# Cockpit-shield.net
KiCad netlist of a schematic drawn in EAGLE
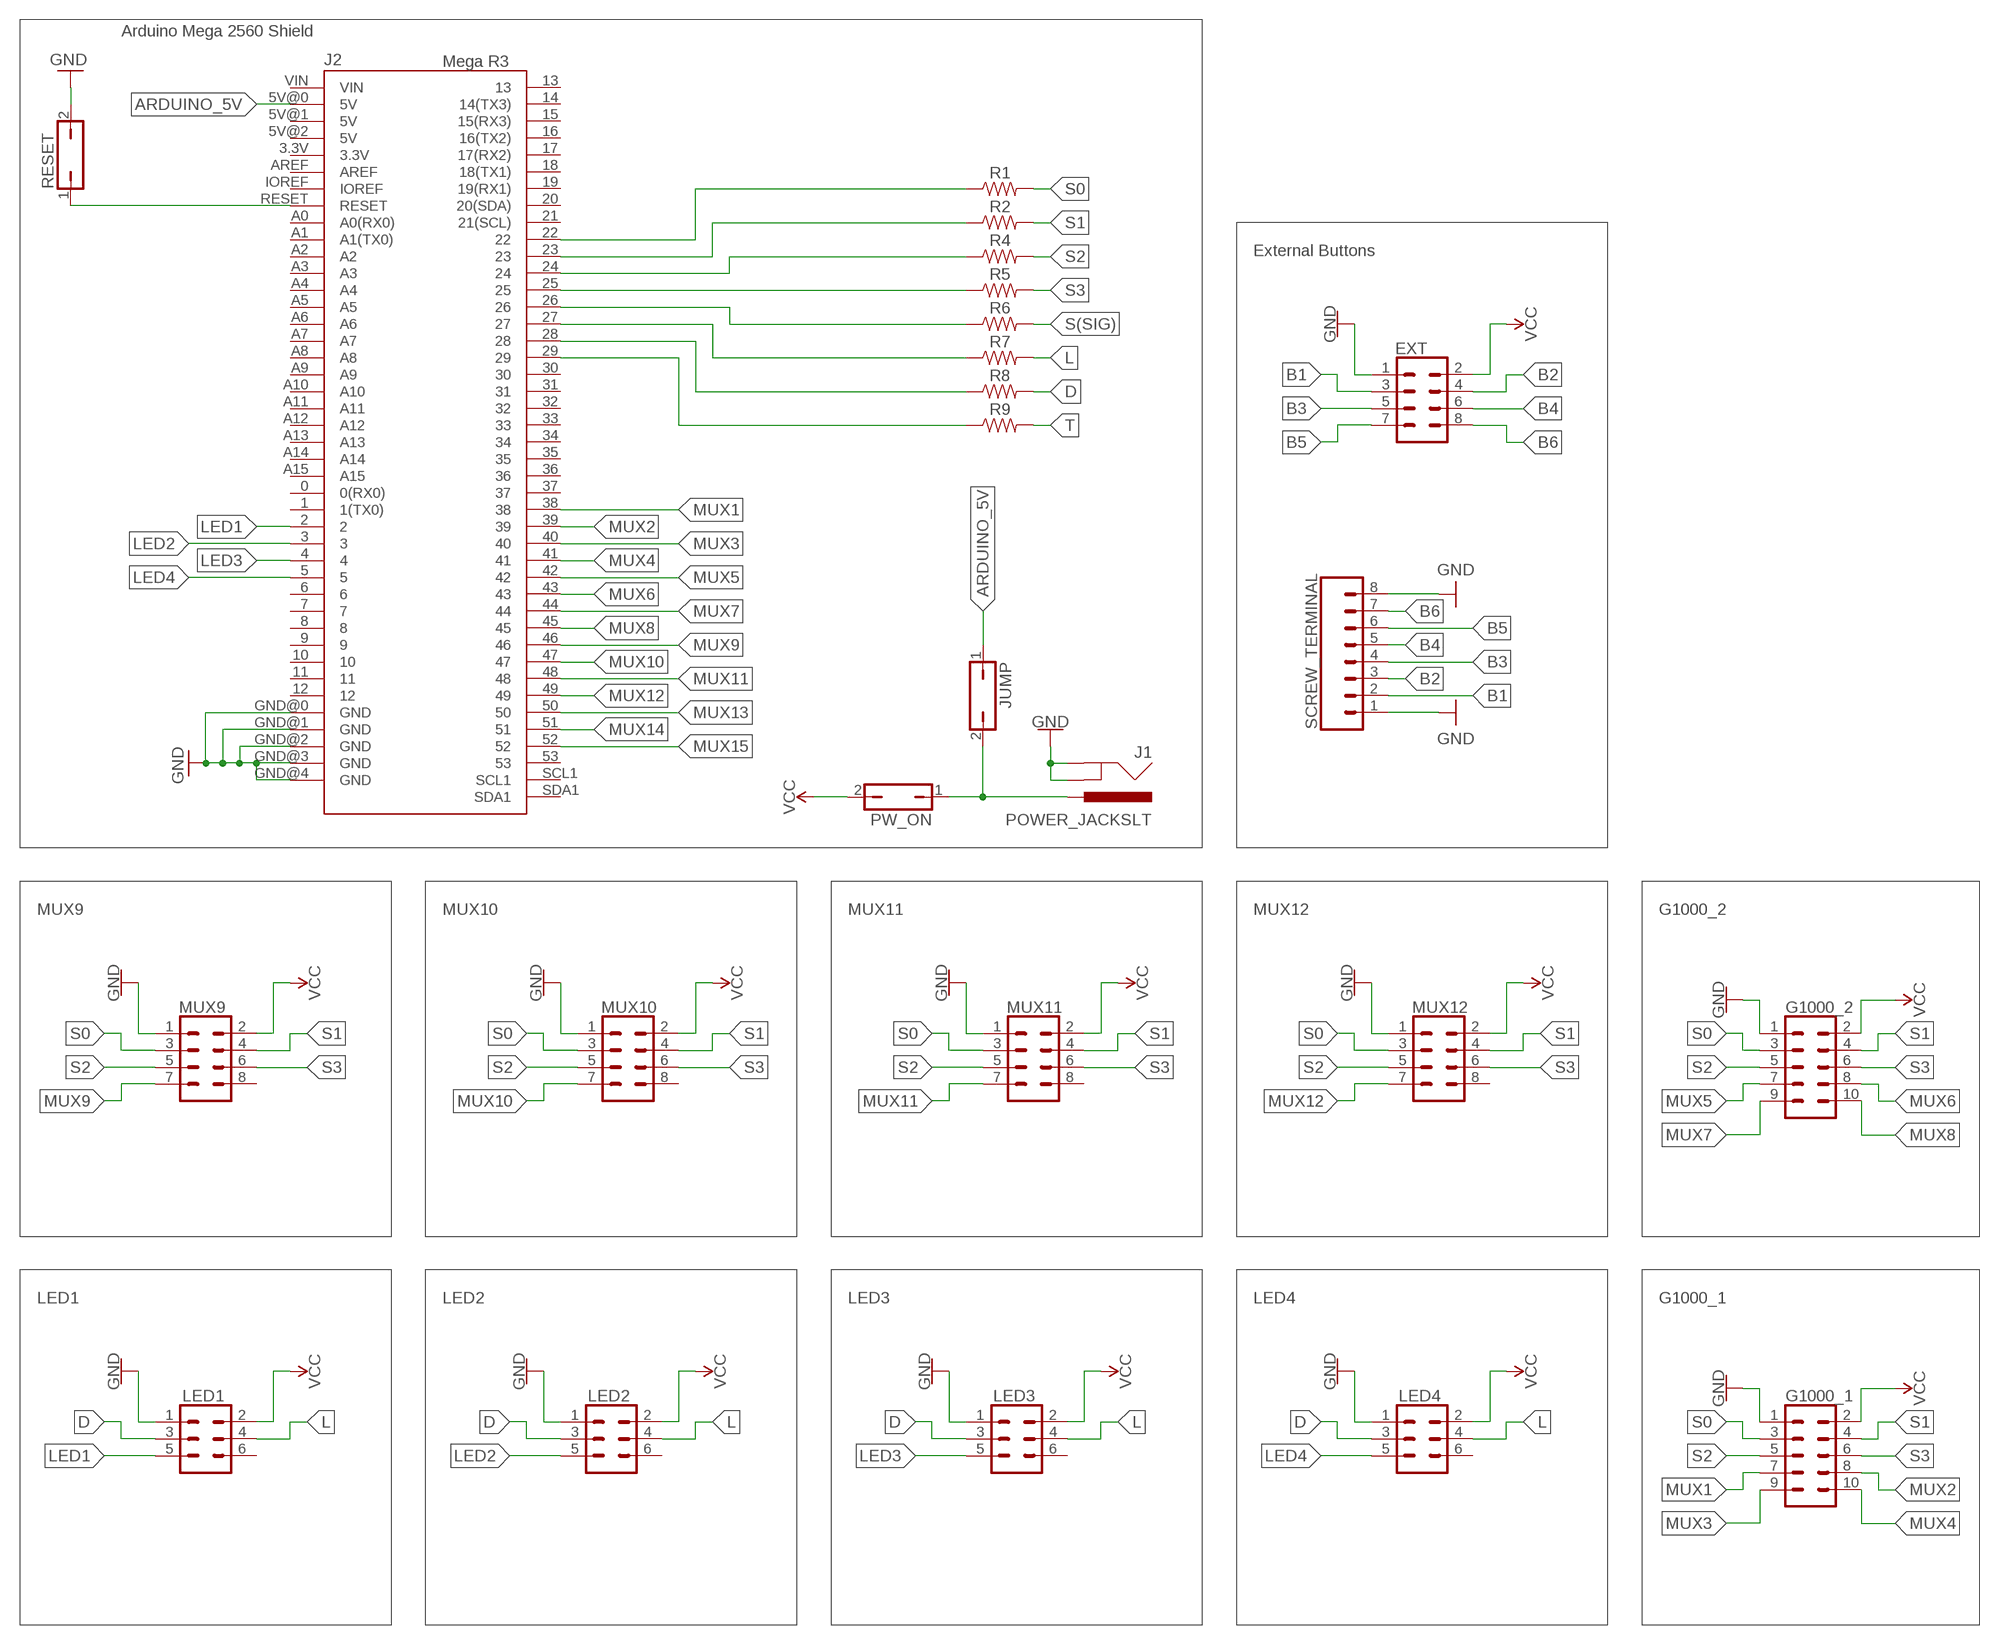
[diagram p0: schematic, sheet 1]

(export (version "E")
  (design (tool "Eeschema 10.0.6"))
  (components
    (comp (ref "EXT")
      (value "CONN_04X2")
      (footprint "eagle-import:2X4")
      (libsource (lib "eagle-import") (part "CONN_04X2"))
    )
    (comp (ref "G1000_1")
      (value "CONN_05X2SHD-NS")
      (footprint "eagle-import:2X5-SHROUDED-NS")
      (libsource (lib "eagle-import") (part "CONN_05X2SHD-NS"))
    )
    (comp (ref "G1000_2")
      (value "CONN_05X2SHD-NS")
      (footprint "eagle-import:2X5-SHROUDED-NS")
      (libsource (lib "eagle-import") (part "CONN_05X2SHD-NS"))
    )
    (comp (ref "J1")
      (value "POWER_JACKSLT")
      (footprint "eagle-import:POWER_JACK_SLOT")
      (libsource (lib "eagle-import") (part "POWER_JACKSLT"))
    )
    (comp (ref "J2")
      (value "Mega R3")
      (footprint "eagle-import:ARDUINO_MEGA")
      (libsource (lib "eagle-import") (part "ARDUINO-MEGAFULL"))
    )
    (comp (ref "JUMP")
      (value "JP1Q")
      (footprint "eagle-import:JP1")
      (libsource (lib "eagle-import") (part "JP1Q"))
    )
    (comp (ref "LED1")
      (value "CONN_03X2NO_SILK")
      (footprint "eagle-import:2X3-NS")
      (libsource (lib "eagle-import") (part "CONN_03X2NO_SILK"))
    )
    (comp (ref "LED2")
      (value "CONN_03X2NO_SILK")
      (footprint "eagle-import:2X3-NS")
      (libsource (lib "eagle-import") (part "CONN_03X2NO_SILK"))
    )
    (comp (ref "LED3")
      (value "CONN_03X2NO_SILK")
      (footprint "eagle-import:2X3-NS")
      (libsource (lib "eagle-import") (part "CONN_03X2NO_SILK"))
    )
    (comp (ref "LED4")
      (value "CONN_03X2NO_SILK")
      (footprint "eagle-import:2X3-NS")
      (libsource (lib "eagle-import") (part "CONN_03X2NO_SILK"))
    )
    (comp (ref "MUX9")
      (value "CONN_04X2")
      (footprint "eagle-import:2X4")
      (libsource (lib "eagle-import") (part "CONN_04X2"))
    )
    (comp (ref "MUX10")
      (value "CONN_04X2")
      (footprint "eagle-import:2X4")
      (libsource (lib "eagle-import") (part "CONN_04X2"))
    )
    (comp (ref "MUX11")
      (value "CONN_04X2")
      (footprint "eagle-import:2X4")
      (libsource (lib "eagle-import") (part "CONN_04X2"))
    )
    (comp (ref "MUX12")
      (value "CONN_04X2")
      (footprint "eagle-import:2X4")
      (libsource (lib "eagle-import") (part "CONN_04X2"))
    )
    (comp (ref "PW_ON")
      (value "JP1Q")
      (footprint "eagle-import:JP1")
      (libsource (lib "eagle-import") (part "JP1Q"))
    )
    (comp (ref "R1")
      (value "RESISTOR1206")
      (footprint "eagle-import:1206")
      (libsource (lib "eagle-import") (part "RESISTOR1206"))
    )
    (comp (ref "R2")
      (value "RESISTOR1206")
      (footprint "eagle-import:1206")
      (libsource (lib "eagle-import") (part "RESISTOR1206"))
    )
    (comp (ref "R4")
      (value "RESISTOR1206")
      (footprint "eagle-import:1206")
      (libsource (lib "eagle-import") (part "RESISTOR1206"))
    )
    (comp (ref "R5")
      (value "RESISTOR1206")
      (footprint "eagle-import:1206")
      (libsource (lib "eagle-import") (part "RESISTOR1206"))
    )
    (comp (ref "R6")
      (value "RESISTOR1206")
      (footprint "eagle-import:1206")
      (libsource (lib "eagle-import") (part "RESISTOR1206"))
    )
    (comp (ref "R7")
      (value "RESISTOR1206")
      (footprint "eagle-import:1206")
      (libsource (lib "eagle-import") (part "RESISTOR1206"))
    )
    (comp (ref "R8")
      (value "RESISTOR1206")
      (footprint "eagle-import:1206")
      (libsource (lib "eagle-import") (part "RESISTOR1206"))
    )
    (comp (ref "R9")
      (value "RESISTOR1206")
      (footprint "eagle-import:1206")
      (libsource (lib "eagle-import") (part "RESISTOR1206"))
    )
    (comp (ref "RESET")
      (value "JP1Q")
      (footprint "eagle-import:JP1")
      (libsource (lib "eagle-import") (part "JP1Q"))
    )
    (comp (ref "SCREW_TERMINAL")
      (value "CONN_083.5MM-8")
      (footprint "eagle-import:SCREWTERMINAL-3.5MM-8")
      (libsource (lib "eagle-import") (part "CONN_083.5MM-8"))
    )
  )
  (nets
    (net (code "1") (name "ARDUINO_5V") (class "Default")
      (node (ref "J2") (pin "5V@0") (pinfunction "5V_5V@0") (pintype "bidirectional"))
      (node (ref "JUMP") (pin "1") (pinfunction "1_1") (pintype "passive"))
    )
    (net (code "2") (name "B1") (class "Default")
      (node (ref "EXT") (pin "3") (pinfunction "3_3") (pintype "passive"))
      (node (ref "SCREW_TERMINAL") (pin "2") (pinfunction "2_2") (pintype "passive"))
    )
    (net (code "3") (name "B2") (class "Default")
      (node (ref "EXT") (pin "4") (pinfunction "4_4") (pintype "passive"))
      (node (ref "SCREW_TERMINAL") (pin "3") (pinfunction "3_3") (pintype "passive"))
    )
    (net (code "4") (name "B3") (class "Default")
      (node (ref "EXT") (pin "5") (pinfunction "5_5") (pintype "passive"))
      (node (ref "SCREW_TERMINAL") (pin "4") (pinfunction "4_4") (pintype "passive"))
    )
    (net (code "5") (name "B4") (class "Default")
      (node (ref "EXT") (pin "6") (pinfunction "6_6") (pintype "passive"))
      (node (ref "SCREW_TERMINAL") (pin "5") (pinfunction "5_5") (pintype "passive"))
    )
    (net (code "6") (name "B5") (class "Default")
      (node (ref "EXT") (pin "7") (pinfunction "7_7") (pintype "passive"))
      (node (ref "SCREW_TERMINAL") (pin "6") (pinfunction "6_6") (pintype "passive"))
    )
    (net (code "7") (name "B6") (class "Default")
      (node (ref "EXT") (pin "8") (pinfunction "8_8") (pintype "passive"))
      (node (ref "SCREW_TERMINAL") (pin "7") (pinfunction "7_7") (pintype "passive"))
    )
    (net (code "8") (name "D") (class "Default")
      (node (ref "LED1") (pin "3") (pinfunction "3_3") (pintype "bidirectional"))
      (node (ref "LED2") (pin "3") (pinfunction "3_3") (pintype "bidirectional"))
      (node (ref "LED3") (pin "3") (pinfunction "3_3") (pintype "bidirectional"))
      (node (ref "LED4") (pin "3") (pinfunction "3_3") (pintype "bidirectional"))
      (node (ref "R8") (pin "2") (pinfunction "2_2") (pintype "passive"))
    )
    (net (code "9") (name "GND") (class "Default")
      (node (ref "EXT") (pin "1") (pinfunction "1_1") (pintype "passive"))
      (node (ref "G1000_1") (pin "1") (pinfunction "1_1") (pintype "passive"))
      (node (ref "G1000_2") (pin "1") (pinfunction "1_1") (pintype "passive"))
      (node (ref "J1") (pin "GND@1") (pinfunction "GNDBREAK_GND@1") (pintype "bidirectional"))
      (node (ref "J1") (pin "GND@2") (pinfunction "GND_GND@2") (pintype "bidirectional"))
      (node (ref "J2") (pin "GND@0") (pinfunction "GND_GND@0") (pintype "bidirectional"))
      (node (ref "J2") (pin "GND@1") (pinfunction "GND_GND@1") (pintype "bidirectional"))
      (node (ref "J2") (pin "GND@2") (pinfunction "GND_GND@2") (pintype "bidirectional"))
      (node (ref "J2") (pin "GND@3") (pinfunction "GND_GND@3") (pintype "bidirectional"))
      (node (ref "J2") (pin "GND@4") (pinfunction "GND_GND@4") (pintype "bidirectional"))
      (node (ref "LED1") (pin "1") (pinfunction "1_1") (pintype "bidirectional"))
      (node (ref "LED2") (pin "1") (pinfunction "1_1") (pintype "bidirectional"))
      (node (ref "LED3") (pin "1") (pinfunction "1_1") (pintype "bidirectional"))
      (node (ref "LED4") (pin "1") (pinfunction "1_1") (pintype "bidirectional"))
      (node (ref "MUX10") (pin "1") (pinfunction "1_1") (pintype "passive"))
      (node (ref "MUX11") (pin "1") (pinfunction "1_1") (pintype "passive"))
      (node (ref "MUX12") (pin "1") (pinfunction "1_1") (pintype "passive"))
      (node (ref "MUX9") (pin "1") (pinfunction "1_1") (pintype "passive"))
      (node (ref "RESET") (pin "2") (pinfunction "2_2") (pintype "passive"))
      (node (ref "SCREW_TERMINAL") (pin "1") (pinfunction "1_1") (pintype "passive"))
      (node (ref "SCREW_TERMINAL") (pin "8") (pinfunction "8_8") (pintype "passive"))
    )
    (net (code "10") (name "L") (class "Default")
      (node (ref "LED1") (pin "4") (pinfunction "4_4") (pintype "bidirectional"))
      (node (ref "LED2") (pin "4") (pinfunction "4_4") (pintype "bidirectional"))
      (node (ref "LED3") (pin "4") (pinfunction "4_4") (pintype "bidirectional"))
      (node (ref "LED4") (pin "4") (pinfunction "4_4") (pintype "bidirectional"))
      (node (ref "R7") (pin "2") (pinfunction "2_2") (pintype "passive"))
    )
    (net (code "11") (name "LED1") (class "Default")
      (node (ref "J2") (pin "2") (pinfunction "2_2") (pintype "bidirectional"))
      (node (ref "LED1") (pin "5") (pinfunction "5_5") (pintype "bidirectional"))
    )
    (net (code "12") (name "LED2") (class "Default")
      (node (ref "J2") (pin "3") (pinfunction "3_3") (pintype "bidirectional"))
      (node (ref "LED2") (pin "5") (pinfunction "5_5") (pintype "bidirectional"))
    )
    (net (code "13") (name "LED3") (class "Default")
      (node (ref "J2") (pin "4") (pinfunction "4_4") (pintype "bidirectional"))
      (node (ref "LED3") (pin "5") (pinfunction "5_5") (pintype "bidirectional"))
    )
    (net (code "14") (name "LED4") (class "Default")
      (node (ref "J2") (pin "5") (pinfunction "5_5") (pintype "bidirectional"))
      (node (ref "LED4") (pin "5") (pinfunction "5_5") (pintype "bidirectional"))
    )
    (net (code "15") (name "MUX1") (class "Default")
      (node (ref "G1000_1") (pin "7") (pinfunction "7_7") (pintype "passive"))
      (node (ref "J2") (pin "38") (pinfunction "38_38") (pintype "bidirectional"))
    )
    (net (code "16") (name "MUX2") (class "Default")
      (node (ref "G1000_1") (pin "8") (pinfunction "8_8") (pintype "passive"))
      (node (ref "J2") (pin "39") (pinfunction "39_39") (pintype "bidirectional"))
    )
    (net (code "17") (name "MUX3") (class "Default")
      (node (ref "G1000_1") (pin "9") (pinfunction "9_9") (pintype "passive"))
      (node (ref "J2") (pin "40") (pinfunction "40_40") (pintype "bidirectional"))
    )
    (net (code "18") (name "MUX4") (class "Default")
      (node (ref "G1000_1") (pin "10") (pinfunction "10_10") (pintype "passive"))
      (node (ref "J2") (pin "41") (pinfunction "41_41") (pintype "bidirectional"))
    )
    (net (code "19") (name "MUX5") (class "Default")
      (node (ref "G1000_2") (pin "7") (pinfunction "7_7") (pintype "passive"))
      (node (ref "J2") (pin "42") (pinfunction "42_42") (pintype "bidirectional"))
    )
    (net (code "20") (name "MUX6") (class "Default")
      (node (ref "G1000_2") (pin "8") (pinfunction "8_8") (pintype "passive"))
      (node (ref "J2") (pin "43") (pinfunction "43_43") (pintype "bidirectional"))
    )
    (net (code "21") (name "MUX7") (class "Default")
      (node (ref "G1000_2") (pin "9") (pinfunction "9_9") (pintype "passive"))
      (node (ref "J2") (pin "44") (pinfunction "44_44") (pintype "bidirectional"))
    )
    (net (code "22") (name "MUX8") (class "Default")
      (node (ref "G1000_2") (pin "10") (pinfunction "10_10") (pintype "passive"))
      (node (ref "J2") (pin "45") (pinfunction "45_45") (pintype "bidirectional"))
    )
    (net (code "23") (name "MUX9") (class "Default")
      (node (ref "J2") (pin "46") (pinfunction "46_46") (pintype "bidirectional"))
      (node (ref "MUX9") (pin "7") (pinfunction "7_7") (pintype "passive"))
    )
    (net (code "24") (name "MUX10") (class "Default")
      (node (ref "J2") (pin "47") (pinfunction "47_47") (pintype "bidirectional"))
      (node (ref "MUX10") (pin "7") (pinfunction "7_7") (pintype "passive"))
    )
    (net (code "25") (name "MUX11") (class "Default")
      (node (ref "J2") (pin "48") (pinfunction "48_48") (pintype "bidirectional"))
      (node (ref "MUX11") (pin "7") (pinfunction "7_7") (pintype "passive"))
    )
    (net (code "26") (name "MUX12") (class "Default")
      (node (ref "J2") (pin "49") (pinfunction "49_49") (pintype "bidirectional"))
      (node (ref "MUX12") (pin "7") (pinfunction "7_7") (pintype "passive"))
    )
    (net (code "27") (name "MUX13") (class "Default")
      (node (ref "J2") (pin "50") (pinfunction "50_50") (pintype "bidirectional"))
    )
    (net (code "28") (name "MUX14") (class "Default")
      (node (ref "J2") (pin "51") (pinfunction "51_51") (pintype "bidirectional"))
    )
    (net (code "29") (name "MUX15") (class "Default")
      (node (ref "J2") (pin "52") (pinfunction "52_52") (pintype "bidirectional"))
    )
    (net (code "30") (name "Net-(J1-PadPWR)") (class "Default")
      (node (ref "J1") (pin "PWR") (pinfunction "PWR_PWR") (pintype "bidirectional"))
      (node (ref "JUMP") (pin "2") (pinfunction "2_2") (pintype "passive"))
      (node (ref "PW_ON") (pin "1") (pinfunction "1_1") (pintype "passive"))
    )
    (net (code "31") (name "Net-(J2-Pad22)") (class "Default")
      (node (ref "J2") (pin "22") (pinfunction "22_22") (pintype "bidirectional"))
      (node (ref "R1") (pin "1") (pinfunction "1_1") (pintype "passive"))
    )
    (net (code "32") (name "Net-(J2-Pad23)") (class "Default")
      (node (ref "J2") (pin "23") (pinfunction "23_23") (pintype "bidirectional"))
      (node (ref "R2") (pin "1") (pinfunction "1_1") (pintype "passive"))
    )
    (net (code "33") (name "Net-(J2-Pad24)") (class "Default")
      (node (ref "J2") (pin "24") (pinfunction "24_24") (pintype "bidirectional"))
      (node (ref "R4") (pin "1") (pinfunction "1_1") (pintype "passive"))
    )
    (net (code "34") (name "Net-(J2-Pad25)") (class "Default")
      (node (ref "J2") (pin "25") (pinfunction "25_25") (pintype "bidirectional"))
      (node (ref "R5") (pin "1") (pinfunction "1_1") (pintype "passive"))
    )
    (net (code "35") (name "Net-(J2-Pad26)") (class "Default")
      (node (ref "J2") (pin "26") (pinfunction "26_26") (pintype "bidirectional"))
      (node (ref "R6") (pin "1") (pinfunction "1_1") (pintype "passive"))
    )
    (net (code "36") (name "Net-(J2-Pad27)") (class "Default")
      (node (ref "J2") (pin "27") (pinfunction "27_27") (pintype "bidirectional"))
      (node (ref "R7") (pin "1") (pinfunction "1_1") (pintype "passive"))
    )
    (net (code "37") (name "Net-(J2-Pad28)") (class "Default")
      (node (ref "J2") (pin "28") (pinfunction "28_28") (pintype "bidirectional"))
      (node (ref "R8") (pin "1") (pinfunction "1_1") (pintype "passive"))
    )
    (net (code "38") (name "Net-(J2-Pad29)") (class "Default")
      (node (ref "J2") (pin "29") (pinfunction "29_29") (pintype "bidirectional"))
      (node (ref "R9") (pin "1") (pinfunction "1_1") (pintype "passive"))
    )
    (net (code "39") (name "Net-(J2-PadRESET)") (class "Default")
      (node (ref "J2") (pin "RESET") (pinfunction "RESET_RESET") (pintype "bidirectional"))
      (node (ref "RESET") (pin "1") (pinfunction "1_1") (pintype "passive"))
    )
    (net (code "40") (name "S(SIG)") (class "Default")
      (node (ref "R6") (pin "2") (pinfunction "2_2") (pintype "passive"))
    )
    (net (code "41") (name "S0") (class "Default")
      (node (ref "G1000_1") (pin "3") (pinfunction "3_3") (pintype "passive"))
      (node (ref "G1000_2") (pin "3") (pinfunction "3_3") (pintype "passive"))
      (node (ref "MUX10") (pin "3") (pinfunction "3_3") (pintype "passive"))
      (node (ref "MUX11") (pin "3") (pinfunction "3_3") (pintype "passive"))
      (node (ref "MUX12") (pin "3") (pinfunction "3_3") (pintype "passive"))
      (node (ref "MUX9") (pin "3") (pinfunction "3_3") (pintype "passive"))
      (node (ref "R1") (pin "2") (pinfunction "2_2") (pintype "passive"))
    )
    (net (code "42") (name "S1") (class "Default")
      (node (ref "G1000_1") (pin "4") (pinfunction "4_4") (pintype "passive"))
      (node (ref "G1000_2") (pin "4") (pinfunction "4_4") (pintype "passive"))
      (node (ref "MUX10") (pin "4") (pinfunction "4_4") (pintype "passive"))
      (node (ref "MUX11") (pin "4") (pinfunction "4_4") (pintype "passive"))
      (node (ref "MUX12") (pin "4") (pinfunction "4_4") (pintype "passive"))
      (node (ref "MUX9") (pin "4") (pinfunction "4_4") (pintype "passive"))
      (node (ref "R2") (pin "2") (pinfunction "2_2") (pintype "passive"))
    )
    (net (code "43") (name "S2") (class "Default")
      (node (ref "G1000_1") (pin "5") (pinfunction "5_5") (pintype "passive"))
      (node (ref "G1000_2") (pin "5") (pinfunction "5_5") (pintype "passive"))
      (node (ref "MUX10") (pin "5") (pinfunction "5_5") (pintype "passive"))
      (node (ref "MUX11") (pin "5") (pinfunction "5_5") (pintype "passive"))
      (node (ref "MUX12") (pin "5") (pinfunction "5_5") (pintype "passive"))
      (node (ref "MUX9") (pin "5") (pinfunction "5_5") (pintype "passive"))
      (node (ref "R4") (pin "2") (pinfunction "2_2") (pintype "passive"))
    )
    (net (code "44") (name "S3") (class "Default")
      (node (ref "G1000_1") (pin "6") (pinfunction "6_6") (pintype "passive"))
      (node (ref "G1000_2") (pin "6") (pinfunction "6_6") (pintype "passive"))
      (node (ref "MUX10") (pin "6") (pinfunction "6_6") (pintype "passive"))
      (node (ref "MUX11") (pin "6") (pinfunction "6_6") (pintype "passive"))
      (node (ref "MUX12") (pin "6") (pinfunction "6_6") (pintype "passive"))
      (node (ref "MUX9") (pin "6") (pinfunction "6_6") (pintype "passive"))
      (node (ref "R5") (pin "2") (pinfunction "2_2") (pintype "passive"))
    )
    (net (code "45") (name "T") (class "Default")
      (node (ref "R9") (pin "2") (pinfunction "2_2") (pintype "passive"))
    )
    (net (code "46") (name "VCC") (class "Default")
      (node (ref "EXT") (pin "2") (pinfunction "2_2") (pintype "passive"))
      (node (ref "G1000_1") (pin "2") (pinfunction "2_2") (pintype "passive"))
      (node (ref "G1000_2") (pin "2") (pinfunction "2_2") (pintype "passive"))
      (node (ref "LED1") (pin "2") (pinfunction "2_2") (pintype "bidirectional"))
      (node (ref "LED2") (pin "2") (pinfunction "2_2") (pintype "bidirectional"))
      (node (ref "LED3") (pin "2") (pinfunction "2_2") (pintype "bidirectional"))
      (node (ref "LED4") (pin "2") (pinfunction "2_2") (pintype "bidirectional"))
      (node (ref "MUX10") (pin "2") (pinfunction "2_2") (pintype "passive"))
      (node (ref "MUX11") (pin "2") (pinfunction "2_2") (pintype "passive"))
      (node (ref "MUX12") (pin "2") (pinfunction "2_2") (pintype "passive"))
      (node (ref "MUX9") (pin "2") (pinfunction "2_2") (pintype "passive"))
      (node (ref "PW_ON") (pin "2") (pinfunction "2_2") (pintype "passive"))
    )
    (net (code "47") (name "unconnected-(J2-0(RX0)-Pad0)") (class "Default")
      (node (ref "J2") (pin "0") (pinfunction "0(RX0)_0") (pintype "bidirectional"))
    )
    (net (code "48") (name "unconnected-(J2-1(TX0)-Pad1)") (class "Default")
      (node (ref "J2") (pin "1") (pinfunction "1(TX0)_1") (pintype "bidirectional"))
    )
    (net (code "49") (name "unconnected-(J2-5V-Pad5V@1)") (class "Default")
      (node (ref "J2") (pin "5V@1") (pinfunction "5V_5V@1") (pintype "bidirectional"))
    )
    (net (code "50") (name "unconnected-(J2-5V-Pad5V@2)") (class "Default")
      (node (ref "J2") (pin "5V@2") (pinfunction "5V_5V@2") (pintype "bidirectional"))
    )
    (net (code "51") (name "unconnected-(J2-14(TX3)-Pad14)") (class "Default")
      (node (ref "J2") (pin "14") (pinfunction "14(TX3)_14") (pintype "bidirectional"))
    )
    (net (code "52") (name "unconnected-(J2-15(RX3)-Pad15)") (class "Default")
      (node (ref "J2") (pin "15") (pinfunction "15(RX3)_15") (pintype "bidirectional"))
    )
    (net (code "53") (name "unconnected-(J2-16(TX2)-Pad16)") (class "Default")
      (node (ref "J2") (pin "16") (pinfunction "16(TX2)_16") (pintype "bidirectional"))
    )
    (net (code "54") (name "unconnected-(J2-17(RX2)-Pad17)") (class "Default")
      (node (ref "J2") (pin "17") (pinfunction "17(RX2)_17") (pintype "bidirectional"))
    )
    (net (code "55") (name "unconnected-(J2-18(TX1)-Pad18)") (class "Default")
      (node (ref "J2") (pin "18") (pinfunction "18(TX1)_18") (pintype "bidirectional"))
    )
    (net (code "56") (name "unconnected-(J2-19(RX1)-Pad19)") (class "Default")
      (node (ref "J2") (pin "19") (pinfunction "19(RX1)_19") (pintype "bidirectional"))
    )
    (net (code "57") (name "unconnected-(J2-20(SDA)-Pad20)") (class "Default")
      (node (ref "J2") (pin "20") (pinfunction "20(SDA)_20") (pintype "bidirectional"))
    )
    (net (code "58") (name "unconnected-(J2-21(SCL)-Pad21)") (class "Default")
      (node (ref "J2") (pin "21") (pinfunction "21(SCL)_21") (pintype "bidirectional"))
    )
    (net (code "59") (name "unconnected-(J2-A0(RX0)-PadA0)") (class "Default")
      (node (ref "J2") (pin "A0") (pinfunction "A0(RX0)_A0") (pintype "bidirectional"))
    )
    (net (code "60") (name "unconnected-(J2-A1(TX0)-PadA1)") (class "Default")
      (node (ref "J2") (pin "A1") (pinfunction "A1(TX0)_A1") (pintype "bidirectional"))
    )
    (net (code "61") (name "unconnected-(J2-Pad3.3V)") (class "Default")
      (node (ref "J2") (pin "3.3V") (pinfunction "3.3V_3.3V") (pintype "bidirectional"))
    )
    (net (code "62") (name "unconnected-(J2-Pad6)") (class "Default")
      (node (ref "J2") (pin "6") (pinfunction "6_6") (pintype "bidirectional"))
    )
    (net (code "63") (name "unconnected-(J2-Pad7)") (class "Default")
      (node (ref "J2") (pin "7") (pinfunction "7_7") (pintype "bidirectional"))
    )
    (net (code "64") (name "unconnected-(J2-Pad8)") (class "Default")
      (node (ref "J2") (pin "8") (pinfunction "8_8") (pintype "bidirectional"))
    )
    (net (code "65") (name "unconnected-(J2-Pad9)") (class "Default")
      (node (ref "J2") (pin "9") (pinfunction "9_9") (pintype "bidirectional"))
    )
    (net (code "66") (name "unconnected-(J2-Pad10)") (class "Default")
      (node (ref "J2") (pin "10") (pinfunction "10_10") (pintype "bidirectional"))
    )
    (net (code "67") (name "unconnected-(J2-Pad11)") (class "Default")
      (node (ref "J2") (pin "11") (pinfunction "11_11") (pintype "bidirectional"))
    )
    (net (code "68") (name "unconnected-(J2-Pad12)") (class "Default")
      (node (ref "J2") (pin "12") (pinfunction "12_12") (pintype "bidirectional"))
    )
    (net (code "69") (name "unconnected-(J2-Pad13)") (class "Default")
      (node (ref "J2") (pin "13") (pinfunction "13_13") (pintype "bidirectional"))
    )
    (net (code "70") (name "unconnected-(J2-Pad30)") (class "Default")
      (node (ref "J2") (pin "30") (pinfunction "30_30") (pintype "bidirectional"))
    )
    (net (code "71") (name "unconnected-(J2-Pad31)") (class "Default")
      (node (ref "J2") (pin "31") (pinfunction "31_31") (pintype "bidirectional"))
    )
    (net (code "72") (name "unconnected-(J2-Pad32)") (class "Default")
      (node (ref "J2") (pin "32") (pinfunction "32_32") (pintype "bidirectional"))
    )
    (net (code "73") (name "unconnected-(J2-Pad33)") (class "Default")
      (node (ref "J2") (pin "33") (pinfunction "33_33") (pintype "bidirectional"))
    )
    (net (code "74") (name "unconnected-(J2-Pad34)") (class "Default")
      (node (ref "J2") (pin "34") (pinfunction "34_34") (pintype "bidirectional"))
    )
    (net (code "75") (name "unconnected-(J2-Pad35)") (class "Default")
      (node (ref "J2") (pin "35") (pinfunction "35_35") (pintype "bidirectional"))
    )
    (net (code "76") (name "unconnected-(J2-Pad36)") (class "Default")
      (node (ref "J2") (pin "36") (pinfunction "36_36") (pintype "bidirectional"))
    )
    (net (code "77") (name "unconnected-(J2-Pad37)") (class "Default")
      (node (ref "J2") (pin "37") (pinfunction "37_37") (pintype "bidirectional"))
    )
    (net (code "78") (name "unconnected-(J2-Pad53)") (class "Default")
      (node (ref "J2") (pin "53") (pinfunction "53_53") (pintype "bidirectional"))
    )
    (net (code "79") (name "unconnected-(J2-PadA2)") (class "Default")
      (node (ref "J2") (pin "A2") (pinfunction "A2_A2") (pintype "bidirectional"))
    )
    (net (code "80") (name "unconnected-(J2-PadA3)") (class "Default")
      (node (ref "J2") (pin "A3") (pinfunction "A3_A3") (pintype "bidirectional"))
    )
    (net (code "81") (name "unconnected-(J2-PadA4)") (class "Default")
      (node (ref "J2") (pin "A4") (pinfunction "A4_A4") (pintype "bidirectional"))
    )
    (net (code "82") (name "unconnected-(J2-PadA5)") (class "Default")
      (node (ref "J2") (pin "A5") (pinfunction "A5_A5") (pintype "bidirectional"))
    )
    (net (code "83") (name "unconnected-(J2-PadA6)") (class "Default")
      (node (ref "J2") (pin "A6") (pinfunction "A6_A6") (pintype "bidirectional"))
    )
    (net (code "84") (name "unconnected-(J2-PadA7)") (class "Default")
      (node (ref "J2") (pin "A7") (pinfunction "A7_A7") (pintype "bidirectional"))
    )
    (net (code "85") (name "unconnected-(J2-PadA8)") (class "Default")
      (node (ref "J2") (pin "A8") (pinfunction "A8_A8") (pintype "bidirectional"))
    )
    (net (code "86") (name "unconnected-(J2-PadA9)") (class "Default")
      (node (ref "J2") (pin "A9") (pinfunction "A9_A9") (pintype "bidirectional"))
    )
    (net (code "87") (name "unconnected-(J2-PadA10)") (class "Default")
      (node (ref "J2") (pin "A10") (pinfunction "A10_A10") (pintype "bidirectional"))
    )
    (net (code "88") (name "unconnected-(J2-PadA11)") (class "Default")
      (node (ref "J2") (pin "A11") (pinfunction "A11_A11") (pintype "bidirectional"))
    )
    (net (code "89") (name "unconnected-(J2-PadA12)") (class "Default")
      (node (ref "J2") (pin "A12") (pinfunction "A12_A12") (pintype "bidirectional"))
    )
    (net (code "90") (name "unconnected-(J2-PadA13)") (class "Default")
      (node (ref "J2") (pin "A13") (pinfunction "A13_A13") (pintype "bidirectional"))
    )
    (net (code "91") (name "unconnected-(J2-PadA14)") (class "Default")
      (node (ref "J2") (pin "A14") (pinfunction "A14_A14") (pintype "bidirectional"))
    )
    (net (code "92") (name "unconnected-(J2-PadA15)") (class "Default")
      (node (ref "J2") (pin "A15") (pinfunction "A15_A15") (pintype "bidirectional"))
    )
    (net (code "93") (name "unconnected-(J2-PadAREF)") (class "Default")
      (node (ref "J2") (pin "AREF") (pinfunction "AREF_AREF") (pintype "bidirectional"))
    )
    (net (code "94") (name "unconnected-(J2-PadIOREF)") (class "Default")
      (node (ref "J2") (pin "IOREF") (pinfunction "IOREF_IOREF") (pintype "bidirectional"))
    )
    (net (code "95") (name "unconnected-(J2-PadSCL1)") (class "Default")
      (node (ref "J2") (pin "SCL1") (pinfunction "SCL1_SCL1") (pintype "bidirectional"))
    )
    (net (code "96") (name "unconnected-(J2-PadSDA1)") (class "Default")
      (node (ref "J2") (pin "SDA1") (pinfunction "SDA1_SDA1") (pintype "bidirectional"))
    )
    (net (code "97") (name "unconnected-(J2-PadVIN)") (class "Default")
      (node (ref "J2") (pin "VIN") (pinfunction "VIN_VIN") (pintype "bidirectional"))
    )
    (net (code "98") (name "unconnected-(LED1-Pad6)") (class "Default")
      (node (ref "LED1") (pin "6") (pinfunction "6_6") (pintype "bidirectional"))
    )
    (net (code "99") (name "unconnected-(LED2-Pad6)") (class "Default")
      (node (ref "LED2") (pin "6") (pinfunction "6_6") (pintype "bidirectional"))
    )
    (net (code "100") (name "unconnected-(LED3-Pad6)") (class "Default")
      (node (ref "LED3") (pin "6") (pinfunction "6_6") (pintype "bidirectional"))
    )
    (net (code "101") (name "unconnected-(LED4-Pad6)") (class "Default")
      (node (ref "LED4") (pin "6") (pinfunction "6_6") (pintype "bidirectional"))
    )
    (net (code "102") (name "unconnected-(MUX9-Pad8)") (class "Default")
      (node (ref "MUX9") (pin "8") (pinfunction "8_8") (pintype "passive"))
    )
    (net (code "103") (name "unconnected-(MUX10-Pad8)") (class "Default")
      (node (ref "MUX10") (pin "8") (pinfunction "8_8") (pintype "passive"))
    )
    (net (code "104") (name "unconnected-(MUX11-Pad8)") (class "Default")
      (node (ref "MUX11") (pin "8") (pinfunction "8_8") (pintype "passive"))
    )
    (net (code "105") (name "unconnected-(MUX12-Pad8)") (class "Default")
      (node (ref "MUX12") (pin "8") (pinfunction "8_8") (pintype "passive"))
    )
  )
)
